# CW32F030C8T6.net
KiCad netlist of a schematic drawn in EasyEDA Pro
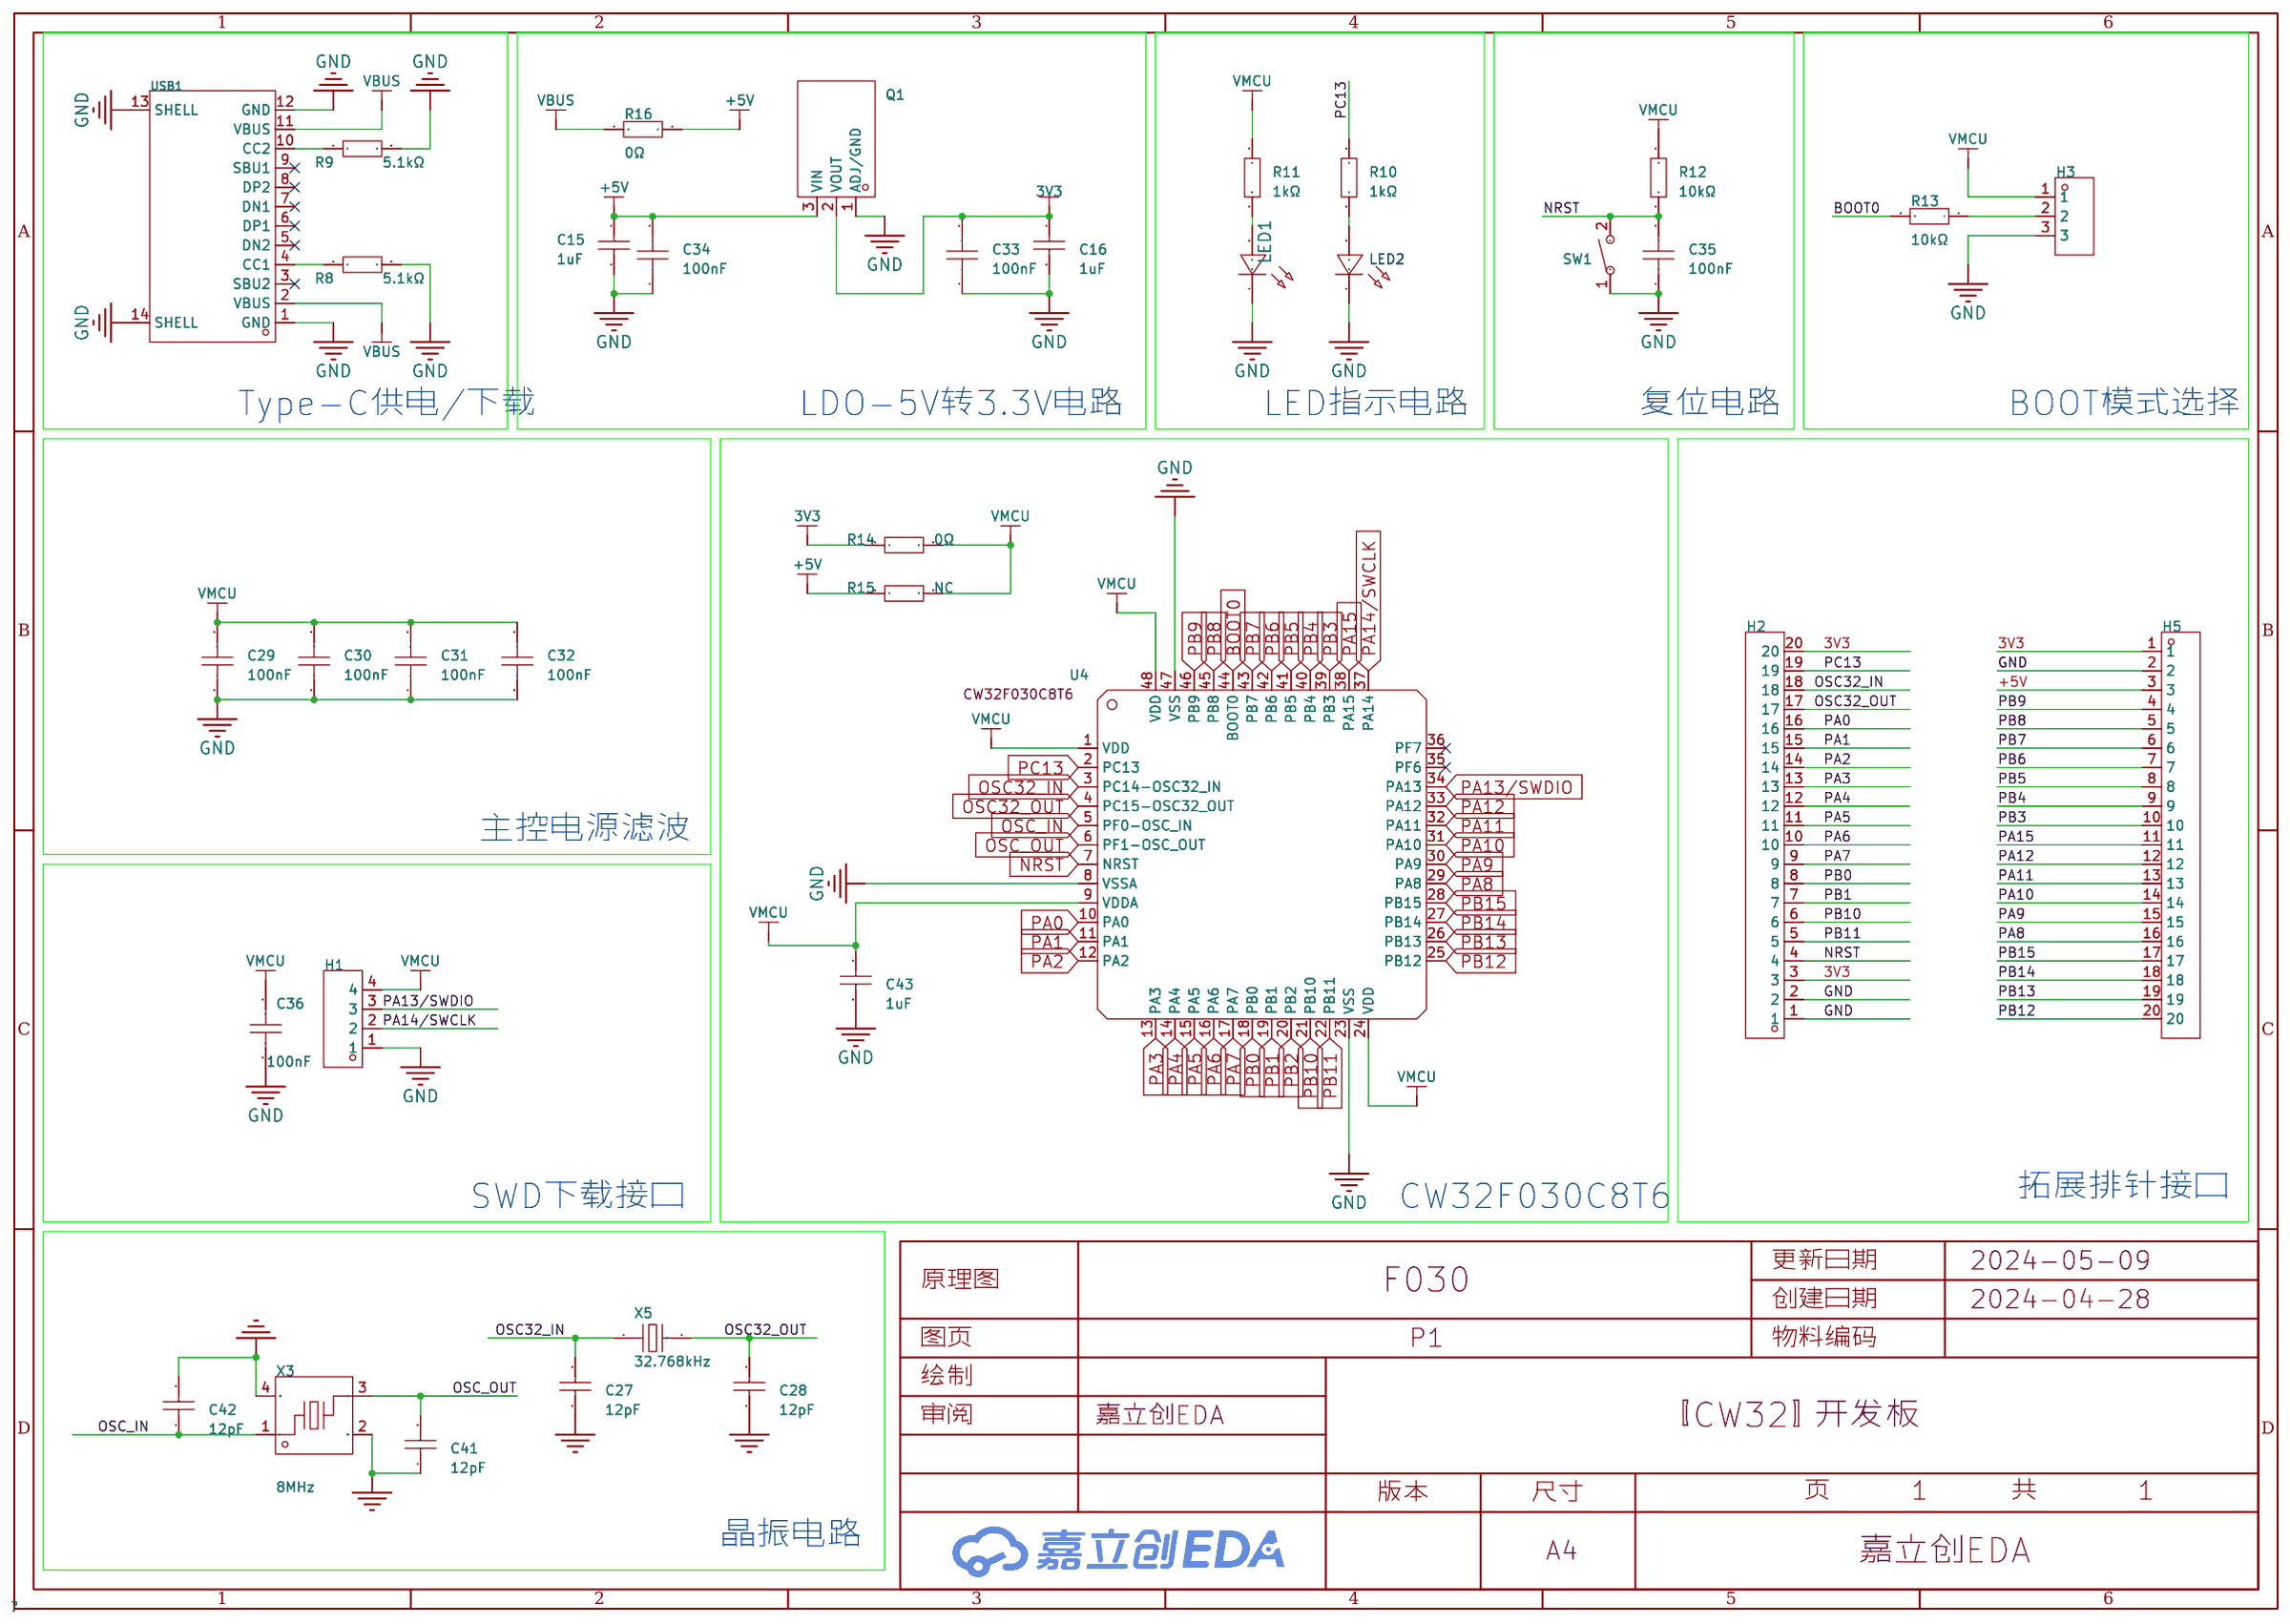
[diagram p0: schematic sheet]

(export (version "E")
  (design (tool "Eeschema 10.0.6"))
  (components
    (comp (ref "C15")
      (value "1uF")
      (footprint "easyedapro:C0402")
      (description "容值:1uF;精度:±10%;额定电压:10V;材质(温度系数):X5R;")
      (fields
        (field (name "Manufacturer Part") "CL10A105KO8NNNC")
        (field (name "Manufacturer") "SAMSUNG(三星)")
      )
      (libsource (lib "easyedapro") (part "CL05A105KP5NNNC"))
    )
    (comp (ref "C16")
      (value "1uF")
      (footprint "easyedapro:C0402")
      (description "容值:1uF;精度:±10%;额定电压:10V;材质(温度系数):X5R;")
      (fields
        (field (name "Manufacturer Part") "CL05A105KP5NNNC")
        (field (name "Manufacturer") "SAMSUNG(三星)")
      )
      (libsource (lib "easyedapro") (part "CL05A105KP5NNNC"))
    )
    (comp (ref "C27")
      (value "12pF")
      (footprint "easyedapro:C0402")
      (description "容值:12pF;精度:±5%;额定电压:50V;材质(温度系数):C0G;")
      (fields (field (name "Manufacturer Part") "0402CG120J500NT") (field (name "Manufacturer") "FH(风华)"))
      (libsource (lib "easyedapro") (part "0402CG120J500NT"))
    )
    (comp (ref "C28")
      (value "12pF")
      (footprint "easyedapro:C0402")
      (description "容值:12pF;精度:±5%;额定电压:50V;材质(温度系数):C0G;")
      (fields (field (name "Manufacturer Part") "0402CG120J500NT") (field (name "Manufacturer") "FH(风华)"))
      (libsource (lib "easyedapro") (part "0402CG120J500NT"))
    )
    (comp (ref "C29")
      (value "100nF")
      (footprint "easyedapro:C0402")
      (description "容值:100nF;精度:±10%;额定电压:50V;材质(温度系数):X7R;")
      (fields
        (field (name "Manufacturer Part") "GRM155R71H104KE14D")
        (field (name "Manufacturer") "muRata(村田)")
      )
      (libsource (lib "easyedapro") (part "GRM155R71H104KE14D"))
    )
    (comp (ref "C30")
      (value "100nF")
      (footprint "easyedapro:C0402")
      (description "容值:100nF;精度:±10%;额定电压:50V;材质(温度系数):X7R;")
      (fields
        (field (name "Manufacturer Part") "GRM155R71H104KE14D")
        (field (name "Manufacturer") "muRata(村田)")
      )
      (libsource (lib "easyedapro") (part "GRM155R71H104KE14D"))
    )
    (comp (ref "C31")
      (value "100nF")
      (footprint "easyedapro:C0402")
      (description "容值:100nF;精度:±10%;额定电压:50V;材质(温度系数):X7R;")
      (fields
        (field (name "Manufacturer Part") "GRM155R71H104KE14D")
        (field (name "Manufacturer") "muRata(村田)")
      )
      (libsource (lib "easyedapro") (part "GRM155R71H104KE14D"))
    )
    (comp (ref "C32")
      (value "100nF")
      (footprint "easyedapro:C0402")
      (description "容值:100nF;精度:±10%;额定电压:50V;材质(温度系数):X7R;")
      (fields
        (field (name "Manufacturer Part") "GRM155R71H104KE14D")
        (field (name "Manufacturer") "muRata(村田)")
      )
      (libsource (lib "easyedapro") (part "GRM155R71H104KE14D"))
    )
    (comp (ref "C33")
      (value "100nF")
      (footprint "easyedapro:C0402")
      (description "容值:100nF;精度:±10%;额定电压:50V;材质(温度系数):X7R;")
      (fields
        (field (name "Manufacturer Part") "GRM155R71H104KE14D")
        (field (name "Manufacturer") "muRata(村田)")
      )
      (libsource (lib "easyedapro") (part "GRM155R71H104KE14D"))
    )
    (comp (ref "C34")
      (value "100nF")
      (footprint "easyedapro:C0402")
      (description "容值:100nF;精度:±10%;额定电压:50V;材质(温度系数):X7R;")
      (fields
        (field (name "Manufacturer Part") "CC0603KRX7R9BB104")
        (field (name "Manufacturer") "YAGEO(国巨)")
      )
      (libsource (lib "easyedapro") (part "GRM155R71H104KE14D"))
    )
    (comp (ref "C35")
      (value "100nF")
      (footprint "easyedapro:C0402")
      (description "容值:100nF;精度:±10%;额定电压:50V;材质(温度系数):X7R;")
      (fields
        (field (name "Manufacturer Part") "GRM155R71H104KE14D")
        (field (name "Manufacturer") "muRata(村田)")
      )
      (libsource (lib "easyedapro") (part "GRM155R71H104KE14D"))
    )
    (comp (ref "C36")
      (value "100nF")
      (footprint "easyedapro:C0402")
      (description "容值:100nF;精度:±10%;额定电压:50V;材质(温度系数):X7R;")
      (fields
        (field (name "Manufacturer Part") "GRM155R71H104KE14D")
        (field (name "Manufacturer") "muRata(村田)")
      )
      (libsource (lib "easyedapro") (part "GRM155R71H104KE14D"))
    )
    (comp (ref "C41")
      (value "12pF")
      (footprint "easyedapro:C0402")
      (description "容值:12pF;精度:±5%;额定电压:50V;材质(温度系数):C0G;")
      (fields (field (name "Manufacturer Part") "0402CG120J500NT") (field (name "Manufacturer") "FH(风华)"))
      (libsource (lib "easyedapro") (part "0402CG120J500NT"))
    )
    (comp (ref "C42")
      (value "12pF")
      (footprint "easyedapro:C0402")
      (description "容值:12pF;精度:±5%;额定电压:50V;材质(温度系数):C0G;")
      (fields (field (name "Manufacturer Part") "0402CG120J500NT") (field (name "Manufacturer") "FH(风华)"))
      (libsource (lib "easyedapro") (part "0402CG120J500NT"))
    )
    (comp (ref "C43")
      (value "1uF")
      (footprint "easyedapro:C0402")
      (description "容值:1uF;精度:±10%;额定电压:10V;材质(温度系数):X5R;")
      (fields
        (field (name "Manufacturer Part") "CL05A105KP5NNNC")
        (field (name "Manufacturer") "SAMSUNG(三星)")
      )
      (libsource (lib "easyedapro") (part "CL05A105KP5NNNC"))
    )
    (comp (ref "H1")
      (value "~")
      (footprint "easyedapro:HDR-TH_4P-P2.54-V-M")
      (libsource (lib "easyedapro") (part "PZ254V-11-04P"))
    )
    (comp (ref "H2")
      (value "~")
      (footprint "easyedapro:HDR-TH_20P-P2.54-V-M-1")
      (libsource (lib "easyedapro") (part "HDR_2.54-1x20P"))
    )
    (comp (ref "H3")
      (value "~")
      (footprint "easyedapro:HDR-TH_3P-P2.54-V-M")
      (libsource (lib "easyedapro") (part "PZ254V-11-03P_C2937625"))
    )
    (comp (ref "H5")
      (value "~")
      (footprint "easyedapro:HDR-TH_20P-P2.54-V-M-1")
      (libsource (lib "easyedapro") (part "HDR_2.54-1x20P"))
    )
    (comp (ref "LED1")
      (value "~")
      (footprint "easyedapro:LED_0603")
      (libsource (lib "easyedapro") (part "LED_R"))
    )
    (comp (ref "LED2")
      (value "~")
      (footprint "easyedapro:LED_0603")
      (libsource (lib "easyedapro") (part "LED_B"))
    )
    (comp (ref "Q1")
      (value "AMS1117-3.3V")
      (footprint "easyedapro:SOT-89-3_L4.5-W2.5-P1.50-LS4.2-BR")
      (description "输出类型:固定;最大输入电压:18V;输出电压:3.3V;最大输出电流:1A;输出极性:正极;")
      (fields (field (name "Manufacturer") "MSKSEMI(美森科)"))
      (libsource (lib "easyedapro") (part "AMS1117-3.3V_C5120796"))
    )
    (comp (ref "R8")
      (value "5.1kΩ")
      (footprint "easyedapro:R0402")
      (description "电阻类型:厚膜电阻;阻值:5.1kΩ;精度:±1%;功率:62.5mW;最大工作电压:50V;温度系数:±100ppm/°C;")
      (fields
        (field (name "Manufacturer Part") "0402WGF5101TCE")
        (field (name "Manufacturer") "UNI-ROYAL(厚声)")
      )
      (libsource (lib "easyedapro") (part "0402WGF5101TCE"))
    )
    (comp (ref "R9")
      (value "5.1kΩ")
      (footprint "easyedapro:R0402")
      (description "电阻类型:厚膜电阻;阻值:5.1kΩ;精度:±1%;功率:62.5mW;最大工作电压:50V;温度系数:±100ppm/°C;")
      (fields
        (field (name "Manufacturer Part") "0402WGF5101TCE")
        (field (name "Manufacturer") "UNI-ROYAL(厚声)")
      )
      (libsource (lib "easyedapro") (part "0402WGF5101TCE"))
    )
    (comp (ref "R10")
      (value "1kΩ")
      (footprint "easyedapro:R0402")
      (description "电阻类型:厚膜电阻;阻值:1kΩ;精度:±1%;功率:62.5mW;最大工作电压:50V;温度系数:±100ppm/°C;")
      (fields
        (field (name "Manufacturer Part") "0402WGF1001TCE")
        (field (name "Manufacturer") "UNI-ROYAL(厚声)")
      )
      (libsource (lib "easyedapro") (part "0402WGF1001TCE"))
    )
    (comp (ref "R11")
      (value "1kΩ")
      (footprint "easyedapro:R0402")
      (description "电阻类型:厚膜电阻;阻值:1kΩ;精度:±1%;功率:62.5mW;最大工作电压:50V;温度系数:±100ppm/°C;")
      (fields
        (field (name "Manufacturer Part") "0402WGF1001TCE")
        (field (name "Manufacturer") "UNI-ROYAL(厚声)")
      )
      (libsource (lib "easyedapro") (part "0402WGF1001TCE"))
    )
    (comp (ref "R12")
      (value "10kΩ")
      (footprint "easyedapro:R0402")
      (description "电阻类型:厚膜电阻;阻值:10kΩ;精度:±1%;功率:62.5mW;最大工作电压:50V;温度系数:±100ppm/°C;")
      (fields (field (name "Manufacturer Part") "RC0402FR-0710KL") (field (name "Manufacturer") "YAGEO(国巨)"))
      (libsource (lib "easyedapro") (part "RC0402FR-0710KL"))
    )
    (comp (ref "R13")
      (value "10kΩ")
      (footprint "easyedapro:R0402")
      (description "电阻类型:厚膜电阻;阻值:10kΩ;精度:±1%;功率:62.5mW;最大工作电压:50V;温度系数:±100ppm/°C;")
      (fields (field (name "Manufacturer Part") "RC0402FR-0710KL") (field (name "Manufacturer") "YAGEO(国巨)"))
      (libsource (lib "easyedapro") (part "RC0402FR-0710KL"))
    )
    (comp (ref "R14")
      (value "0Ω")
      (footprint "easyedapro:R0805")
      (description "电阻类型:厚膜电阻;阻值:0Ω;精度:±1%;功率:125mW;最大工作电压:150V;温度系数:±800ppm/°C;")
      (fields
        (field (name "Manufacturer Part") "0805W8F0000T5E")
        (field (name "Manufacturer") "UNI-ROYAL(厚声)")
      )
      (libsource (lib "easyedapro") (part "0805W8F0000T5E"))
    )
    (comp (ref "R15")
      (value "NC")
      (footprint "easyedapro:R0805")
      (description "电阻类型:厚膜电阻;阻值:0Ω;精度:±1%;功率:125mW;最大工作电压:150V;温度系数:±800ppm/°C;")
      (fields
        (field (name "Manufacturer Part") "0805W8F0000T5E")
        (field (name "Manufacturer") "UNI-ROYAL(厚声)")
      )
      (libsource (lib "easyedapro") (part "0805W8F0000T5E"))
    )
    (comp (ref "R16")
      (value "0Ω")
      (footprint "easyedapro:R0603")
      (description "电阻类型:厚膜电阻;阻值:0Ω;精度:±1%;功率:100mW;最大工作电压:75V;")
      (fields
        (field (name "Manufacturer Part") "0603WAF0000T5E")
        (field (name "Manufacturer") "UNI-ROYAL(厚声)")
      )
      (libsource (lib "easyedapro") (part "0603WAF0000T5E"))
    )
    (comp (ref "SW1")
      (value "TS-1101-B-W")
      (footprint "easyedapro:KEY-SMD_2P-L6.0-W3.6-P7.4-LS8.0-L")
      (description "触点电流:50mA;额定电压(DC):12V;绝缘电阻:-;电路结构:单刀单掷;安装方式:立贴;带灯:无;作用力:160gf;机械寿命:5万次;带支架:否;")
      (fields (field (name "Manufacturer") "XKB Connectivity(中国星坤)"))
      (libsource (lib "easyedapro") (part "TS-1101-B-W"))
    )
    (comp (ref "U4")
      (value "CW32F030C8T6")
      (footprint "easyedapro:LQFP-48_L7.0-W7.0-P0.50-LS9.0-TL")
      (description "CPU内核:ARM-M系列;RAM总容量:8KB;GPIO端口数量:39;工作电压范围:1.65V~5.5V;CPU最大主频:64MHz;程序存储器类型:-;")
      (fields (field (name "Manufacturer Part") "CW32F030C8T6") (field (name "Manufacturer") "CW(芯源)"))
      (libsource (lib "easyedapro") (part "CW32F030C8T6_C3019113"))
    )
    (comp (ref "USB1")
      (value "TYPE-C 16PIN 2MD(073)")
      (footprint "easyedapro:USB-C-SMD_TYPE-C-6PIN-2MD-073")
      (description "连接器类型:Type-C;标准:-;公母:母座;触点数量:16;端口数量:1;安装方式:卧贴;额定电流 - 电源:5A;工作温度范围:-25°C~+85°C;")
      (fields (field (name "Manufacturer") "SHOU HAN(首韩)"))
      (libsource (lib "easyedapro") (part "TYPE-C 16PIN 2MD(073)"))
    )
    (comp (ref "X3")
      (value "8MHz")
      (footprint "easyedapro:CRYSTAL-SMD_4P-L3.2-W2.5-BL-1")
      (description "晶振类型:贴片晶振;频率:8MHz;常温频差:±10ppm;外接负载电容:12pF;频率稳定度(全温):±20ppm;")
      (fields
        (field (name "Manufacturer Part") "XL2EL89COI-111YLC-8M")
        (field (name "Manufacturer") "YXC(扬兴晶振)")
      )
      (libsource (lib "easyedapro") (part "XL2EL89COI-111YLC-8M"))
    )
    (comp (ref "X5")
      (value "32.768kHz")
      (footprint "easyedapro:OSC-SMD_L3.2-W1.5")
      (description "晶振类型:贴片晶振;频率:32.768kHz;常温频差:±20ppm;外接负载电容:12.5pF;频率稳定度(全温):-;")
      (fields (field (name "Manufacturer Part") "X321532768KGD2SI") (field (name "Manufacturer") "YXC(扬兴晶振)"))
      (libsource (lib "easyedapro") (part "X321532768KGD2SI"))
    )
  )
  (nets
    (net (code "1") (name "+5V") (class "Default")
      (node (ref "C15") (pin "2") (pinfunction "2_2") (pintype "input"))
      (node (ref "C34") (pin "2") (pinfunction "2_2") (pintype "unspecified"))
      (node (ref "H5") (pin "3") (pinfunction "3_3") (pintype "input"))
      (node (ref "Q1") (pin "3") (pinfunction "VIN_3") (pintype "unspecified"))
      (node (ref "R15") (pin "1") (pinfunction "1_1") (pintype "input"))
      (node (ref "R16") (pin "2") (pinfunction "2_2") (pintype "input"))
    )
    (net (code "2") (name "3V3") (class "Default")
      (node (ref "C16") (pin "2") (pinfunction "2_2") (pintype "input"))
      (node (ref "C33") (pin "2") (pinfunction "2_2") (pintype "unspecified"))
      (node (ref "H2") (pin "20") (pinfunction "20_20") (pintype "input"))
      (node (ref "H2") (pin "3") (pinfunction "3_3") (pintype "input"))
      (node (ref "H5") (pin "1") (pinfunction "1_1") (pintype "input"))
      (node (ref "Q1") (pin "2") (pinfunction "VOUT_2") (pintype "unspecified"))
      (node (ref "R14") (pin "1") (pinfunction "1_1") (pintype "input"))
    )
    (net (code "3") (name "BOOT0") (class "Default")
      (node (ref "R13") (pin "2") (pinfunction "2_2") (pintype "input"))
      (node (ref "U4") (pin "44") (pinfunction "BOOT0_44") (pintype "unspecified"))
    )
    (net (code "4") (name "GND") (class "Default")
      (node (ref "C15") (pin "1") (pinfunction "1_1") (pintype "input"))
      (node (ref "C16") (pin "1") (pinfunction "1_1") (pintype "input"))
      (node (ref "C27") (pin "1") (pinfunction "1_1") (pintype "input"))
      (node (ref "C28") (pin "1") (pinfunction "1_1") (pintype "input"))
      (node (ref "C29") (pin "1") (pinfunction "1_1") (pintype "unspecified"))
      (node (ref "C30") (pin "1") (pinfunction "1_1") (pintype "unspecified"))
      (node (ref "C31") (pin "1") (pinfunction "1_1") (pintype "unspecified"))
      (node (ref "C32") (pin "1") (pinfunction "1_1") (pintype "unspecified"))
      (node (ref "C33") (pin "1") (pinfunction "1_1") (pintype "unspecified"))
      (node (ref "C34") (pin "1") (pinfunction "1_1") (pintype "unspecified"))
      (node (ref "C35") (pin "1") (pinfunction "1_1") (pintype "unspecified"))
      (node (ref "C36") (pin "1") (pinfunction "1_1") (pintype "unspecified"))
      (node (ref "C41") (pin "1") (pinfunction "1_1") (pintype "input"))
      (node (ref "C42") (pin "2") (pinfunction "2_2") (pintype "input"))
      (node (ref "C43") (pin "1") (pinfunction "1_1") (pintype "input"))
      (node (ref "H1") (pin "1") (pinfunction "1_1") (pintype "input"))
      (node (ref "H2") (pin "1") (pinfunction "1_1") (pintype "input"))
      (node (ref "H2") (pin "2") (pinfunction "2_2") (pintype "input"))
      (node (ref "H3") (pin "3") (pinfunction "3_3") (pintype "input"))
      (node (ref "H5") (pin "2") (pinfunction "2_2") (pintype "input"))
      (node (ref "LED1") (pin "1") (pinfunction "C_1") (pintype "input"))
      (node (ref "LED2") (pin "1") (pinfunction "C_1") (pintype "input"))
      (node (ref "Q1") (pin "1") (pinfunction "ADJ/GND_1") (pintype "unspecified"))
      (node (ref "R8") (pin "2") (pinfunction "2_2") (pintype "input"))
      (node (ref "R9") (pin "2") (pinfunction "2_2") (pintype "input"))
      (node (ref "SW1") (pin "1") (pinfunction "1_1") (pintype "input"))
      (node (ref "U4") (pin "23") (pinfunction "VSS_23") (pintype "unspecified"))
      (node (ref "U4") (pin "47") (pinfunction "VSS_47") (pintype "unspecified"))
      (node (ref "U4") (pin "8") (pinfunction "VSSA_8") (pintype "unspecified"))
      (node (ref "USB1") (pin "1") (pinfunction "GND_1") (pintype "input"))
      (node (ref "USB1") (pin "12") (pinfunction "GND_12") (pintype "input"))
      (node (ref "USB1") (pin "13") (pinfunction "SHELL_13") (pintype "input"))
      (node (ref "USB1") (pin "14") (pinfunction "SHELL_14") (pintype "input"))
      (node (ref "X3") (pin "2") (pinfunction "GND_2") (pintype "input"))
      (node (ref "X3") (pin "4") (pinfunction "GND_4") (pintype "input"))
    )
    (net (code "5") (name "NRST") (class "Default")
      (node (ref "C35") (pin "2") (pinfunction "2_2") (pintype "unspecified"))
      (node (ref "H2") (pin "4") (pinfunction "4_4") (pintype "input"))
      (node (ref "R12") (pin "1") (pinfunction "1_1") (pintype "input"))
      (node (ref "SW1") (pin "2") (pinfunction "2_2") (pintype "input"))
      (node (ref "U4") (pin "7") (pinfunction "NRST_7") (pintype "unspecified"))
    )
    (net (code "6") (name "Net-(H3-Pad2)") (class "Default")
      (node (ref "H3") (pin "2") (pinfunction "2_2") (pintype "input"))
      (node (ref "R13") (pin "1") (pinfunction "1_1") (pintype "input"))
    )
    (net (code "7") (name "Net-(LED1-A)") (class "Default")
      (node (ref "LED1") (pin "2") (pinfunction "A_2") (pintype "input"))
      (node (ref "R11") (pin "2") (pinfunction "2_2") (pintype "input"))
    )
    (net (code "8") (name "Net-(LED2-A)") (class "Default")
      (node (ref "LED2") (pin "2") (pinfunction "A_2") (pintype "input"))
      (node (ref "R10") (pin "1") (pinfunction "1_1") (pintype "input"))
    )
    (net (code "9") (name "Net-(USB1-CC1)") (class "Default")
      (node (ref "R8") (pin "1") (pinfunction "1_1") (pintype "input"))
      (node (ref "USB1") (pin "4") (pinfunction "CC1_4") (pintype "input"))
    )
    (net (code "10") (name "Net-(USB1-CC2)") (class "Default")
      (node (ref "R9") (pin "1") (pinfunction "1_1") (pintype "input"))
      (node (ref "USB1") (pin "10") (pinfunction "CC2_10") (pintype "input"))
    )
    (net (code "11") (name "OSC32_IN") (class "Default")
      (node (ref "C27") (pin "2") (pinfunction "2_2") (pintype "input"))
      (node (ref "H2") (pin "18") (pinfunction "18_18") (pintype "input"))
      (node (ref "U4") (pin "3") (pinfunction "PC14-OSC32_IN_3") (pintype "unspecified"))
      (node (ref "X5") (pin "1") (pinfunction "1_1") (pintype "input"))
    )
    (net (code "12") (name "OSC32_OUT") (class "Default")
      (node (ref "C28") (pin "2") (pinfunction "2_2") (pintype "input"))
      (node (ref "H2") (pin "17") (pinfunction "17_17") (pintype "input"))
      (node (ref "U4") (pin "4") (pinfunction "PC15-OSC32_OUT_4") (pintype "unspecified"))
      (node (ref "X5") (pin "2") (pinfunction "2_2") (pintype "input"))
    )
    (net (code "13") (name "OSC_IN") (class "Default")
      (node (ref "C42") (pin "1") (pinfunction "1_1") (pintype "input"))
      (node (ref "U4") (pin "5") (pinfunction "PF0-OSC_IN_5") (pintype "unspecified"))
      (node (ref "X3") (pin "1") (pinfunction "1_1") (pintype "input"))
    )
    (net (code "14") (name "OSC_OUT") (class "Default")
      (node (ref "C41") (pin "2") (pinfunction "2_2") (pintype "input"))
      (node (ref "U4") (pin "6") (pinfunction "PF1-OSC_OUT_6") (pintype "unspecified"))
      (node (ref "X3") (pin "3") (pinfunction "3_3") (pintype "input"))
    )
    (net (code "15") (name "PA0") (class "Default")
      (node (ref "H2") (pin "16") (pinfunction "16_16") (pintype "input"))
      (node (ref "U4") (pin "10") (pinfunction "PA0_10") (pintype "unspecified"))
    )
    (net (code "16") (name "PA1") (class "Default")
      (node (ref "H2") (pin "15") (pinfunction "15_15") (pintype "input"))
      (node (ref "U4") (pin "11") (pinfunction "PA1_11") (pintype "unspecified"))
    )
    (net (code "17") (name "PA2") (class "Default")
      (node (ref "H2") (pin "14") (pinfunction "14_14") (pintype "input"))
      (node (ref "U4") (pin "12") (pinfunction "PA2_12") (pintype "unspecified"))
    )
    (net (code "18") (name "PA3") (class "Default")
      (node (ref "H2") (pin "13") (pinfunction "13_13") (pintype "input"))
      (node (ref "U4") (pin "13") (pinfunction "PA3_13") (pintype "unspecified"))
    )
    (net (code "19") (name "PA4") (class "Default")
      (node (ref "H2") (pin "12") (pinfunction "12_12") (pintype "input"))
      (node (ref "U4") (pin "14") (pinfunction "PA4_14") (pintype "unspecified"))
    )
    (net (code "20") (name "PA5") (class "Default")
      (node (ref "H2") (pin "11") (pinfunction "11_11") (pintype "input"))
      (node (ref "U4") (pin "15") (pinfunction "PA5_15") (pintype "unspecified"))
    )
    (net (code "21") (name "PA6") (class "Default")
      (node (ref "H2") (pin "10") (pinfunction "10_10") (pintype "input"))
      (node (ref "U4") (pin "16") (pinfunction "PA6_16") (pintype "unspecified"))
    )
    (net (code "22") (name "PA7") (class "Default")
      (node (ref "H2") (pin "9") (pinfunction "9_9") (pintype "input"))
      (node (ref "U4") (pin "17") (pinfunction "PA7_17") (pintype "unspecified"))
    )
    (net (code "23") (name "PA8") (class "Default")
      (node (ref "H5") (pin "16") (pinfunction "16_16") (pintype "input"))
      (node (ref "U4") (pin "29") (pinfunction "PA8_29") (pintype "unspecified"))
    )
    (net (code "24") (name "PA9") (class "Default")
      (node (ref "H5") (pin "15") (pinfunction "15_15") (pintype "input"))
      (node (ref "U4") (pin "30") (pinfunction "PA9_30") (pintype "unspecified"))
    )
    (net (code "25") (name "PA10") (class "Default")
      (node (ref "H5") (pin "14") (pinfunction "14_14") (pintype "input"))
      (node (ref "U4") (pin "31") (pinfunction "PA10_31") (pintype "unspecified"))
    )
    (net (code "26") (name "PA11") (class "Default")
      (node (ref "H5") (pin "13") (pinfunction "13_13") (pintype "input"))
      (node (ref "U4") (pin "32") (pinfunction "PA11_32") (pintype "unspecified"))
    )
    (net (code "27") (name "PA12") (class "Default")
      (node (ref "H5") (pin "12") (pinfunction "12_12") (pintype "input"))
      (node (ref "U4") (pin "33") (pinfunction "PA12_33") (pintype "unspecified"))
    )
    (net (code "28") (name "PA13{slash}SWDIO") (class "Default")
      (node (ref "H1") (pin "3") (pinfunction "3_3") (pintype "input"))
      (node (ref "U4") (pin "34") (pinfunction "PA13_34") (pintype "unspecified"))
    )
    (net (code "29") (name "PA14{slash}SWCLK") (class "Default")
      (node (ref "H1") (pin "2") (pinfunction "2_2") (pintype "input"))
      (node (ref "U4") (pin "37") (pinfunction "PA14_37") (pintype "unspecified"))
    )
    (net (code "30") (name "PA15") (class "Default")
      (node (ref "H5") (pin "11") (pinfunction "11_11") (pintype "input"))
      (node (ref "U4") (pin "38") (pinfunction "PA15_38") (pintype "unspecified"))
    )
    (net (code "31") (name "PB0") (class "Default")
      (node (ref "H2") (pin "8") (pinfunction "8_8") (pintype "input"))
      (node (ref "U4") (pin "18") (pinfunction "PB0_18") (pintype "unspecified"))
    )
    (net (code "32") (name "PB1") (class "Default")
      (node (ref "H2") (pin "7") (pinfunction "7_7") (pintype "input"))
      (node (ref "U4") (pin "19") (pinfunction "PB1_19") (pintype "unspecified"))
    )
    (net (code "33") (name "PB2") (class "Default")
      (node (ref "U4") (pin "20") (pinfunction "PB2_20") (pintype "unspecified"))
    )
    (net (code "34") (name "PB3") (class "Default")
      (node (ref "H5") (pin "10") (pinfunction "10_10") (pintype "input"))
      (node (ref "U4") (pin "39") (pinfunction "PB3_39") (pintype "unspecified"))
    )
    (net (code "35") (name "PB4") (class "Default")
      (node (ref "H5") (pin "9") (pinfunction "9_9") (pintype "input"))
      (node (ref "U4") (pin "40") (pinfunction "PB4_40") (pintype "unspecified"))
    )
    (net (code "36") (name "PB5") (class "Default")
      (node (ref "H5") (pin "8") (pinfunction "8_8") (pintype "input"))
      (node (ref "U4") (pin "41") (pinfunction "PB5_41") (pintype "unspecified"))
    )
    (net (code "37") (name "PB6") (class "Default")
      (node (ref "H5") (pin "7") (pinfunction "7_7") (pintype "input"))
      (node (ref "U4") (pin "42") (pinfunction "PB6_42") (pintype "unspecified"))
    )
    (net (code "38") (name "PB7") (class "Default")
      (node (ref "H5") (pin "6") (pinfunction "6_6") (pintype "input"))
      (node (ref "U4") (pin "43") (pinfunction "PB7_43") (pintype "unspecified"))
    )
    (net (code "39") (name "PB8") (class "Default")
      (node (ref "H5") (pin "5") (pinfunction "5_5") (pintype "input"))
      (node (ref "U4") (pin "45") (pinfunction "PB8_45") (pintype "unspecified"))
    )
    (net (code "40") (name "PB9") (class "Default")
      (node (ref "H5") (pin "4") (pinfunction "4_4") (pintype "input"))
      (node (ref "U4") (pin "46") (pinfunction "PB9_46") (pintype "unspecified"))
    )
    (net (code "41") (name "PB10") (class "Default")
      (node (ref "H2") (pin "6") (pinfunction "6_6") (pintype "input"))
      (node (ref "U4") (pin "21") (pinfunction "PB10_21") (pintype "unspecified"))
    )
    (net (code "42") (name "PB11") (class "Default")
      (node (ref "H2") (pin "5") (pinfunction "5_5") (pintype "input"))
      (node (ref "U4") (pin "22") (pinfunction "PB11_22") (pintype "unspecified"))
    )
    (net (code "43") (name "PB12") (class "Default")
      (node (ref "H5") (pin "20") (pinfunction "20_20") (pintype "input"))
      (node (ref "U4") (pin "25") (pinfunction "PB12_25") (pintype "unspecified"))
    )
    (net (code "44") (name "PB13") (class "Default")
      (node (ref "H5") (pin "19") (pinfunction "19_19") (pintype "input"))
      (node (ref "U4") (pin "26") (pinfunction "PB13_26") (pintype "unspecified"))
    )
    (net (code "45") (name "PB14") (class "Default")
      (node (ref "H5") (pin "18") (pinfunction "18_18") (pintype "input"))
      (node (ref "U4") (pin "27") (pinfunction "PB14_27") (pintype "unspecified"))
    )
    (net (code "46") (name "PB15") (class "Default")
      (node (ref "H5") (pin "17") (pinfunction "17_17") (pintype "input"))
      (node (ref "U4") (pin "28") (pinfunction "PB15_28") (pintype "unspecified"))
    )
    (net (code "47") (name "PC13") (class "Default")
      (node (ref "H2") (pin "19") (pinfunction "19_19") (pintype "input"))
      (node (ref "R10") (pin "2") (pinfunction "2_2") (pintype "input"))
      (node (ref "U4") (pin "2") (pinfunction "PC13_2") (pintype "unspecified"))
    )
    (net (code "48") (name "VBUS") (class "Default")
      (node (ref "R16") (pin "1") (pinfunction "1_1") (pintype "input"))
      (node (ref "USB1") (pin "11") (pinfunction "VBUS_11") (pintype "input"))
      (node (ref "USB1") (pin "2") (pinfunction "VBUS_2") (pintype "input"))
    )
    (net (code "49") (name "VMCU") (class "Default")
      (node (ref "C29") (pin "2") (pinfunction "2_2") (pintype "unspecified"))
      (node (ref "C30") (pin "2") (pinfunction "2_2") (pintype "unspecified"))
      (node (ref "C31") (pin "2") (pinfunction "2_2") (pintype "unspecified"))
      (node (ref "C32") (pin "2") (pinfunction "2_2") (pintype "unspecified"))
      (node (ref "C36") (pin "2") (pinfunction "2_2") (pintype "unspecified"))
      (node (ref "C43") (pin "2") (pinfunction "2_2") (pintype "input"))
      (node (ref "H1") (pin "4") (pinfunction "4_4") (pintype "input"))
      (node (ref "H3") (pin "1") (pinfunction "1_1") (pintype "input"))
      (node (ref "R11") (pin "1") (pinfunction "1_1") (pintype "input"))
      (node (ref "R12") (pin "2") (pinfunction "2_2") (pintype "input"))
      (node (ref "R14") (pin "2") (pinfunction "2_2") (pintype "input"))
      (node (ref "R15") (pin "2") (pinfunction "2_2") (pintype "input"))
      (node (ref "U4") (pin "1") (pinfunction "VDD_1") (pintype "unspecified"))
      (node (ref "U4") (pin "24") (pinfunction "VDD_24") (pintype "unspecified"))
      (node (ref "U4") (pin "48") (pinfunction "VDD_48") (pintype "unspecified"))
      (node (ref "U4") (pin "9") (pinfunction "VDDA_9") (pintype "unspecified"))
    )
    (net (code "50") (name "unconnected-(U4-PF6-Pad35)") (class "Default")
      (node (ref "U4") (pin "35") (pinfunction "PF6_35") (pintype "unspecified+no_connect"))
    )
    (net (code "51") (name "unconnected-(U4-PF7-Pad36)") (class "Default")
      (node (ref "U4") (pin "36") (pinfunction "PF7_36") (pintype "unspecified+no_connect"))
    )
    (net (code "52") (name "unconnected-(USB1-DN1-Pad7)") (class "Default")
      (node (ref "USB1") (pin "7") (pinfunction "DN1_7") (pintype "input+no_connect"))
    )
    (net (code "53") (name "unconnected-(USB1-DN2-Pad5)") (class "Default")
      (node (ref "USB1") (pin "5") (pinfunction "DN2_5") (pintype "input+no_connect"))
    )
    (net (code "54") (name "unconnected-(USB1-DP1-Pad6)") (class "Default")
      (node (ref "USB1") (pin "6") (pinfunction "DP1_6") (pintype "input+no_connect"))
    )
    (net (code "55") (name "unconnected-(USB1-DP2-Pad8)") (class "Default")
      (node (ref "USB1") (pin "8") (pinfunction "DP2_8") (pintype "input+no_connect"))
    )
    (net (code "56") (name "unconnected-(USB1-SBU1-Pad9)") (class "Default")
      (node (ref "USB1") (pin "9") (pinfunction "SBU1_9") (pintype "input+no_connect"))
    )
    (net (code "57") (name "unconnected-(USB1-SBU2-Pad3)") (class "Default")
      (node (ref "USB1") (pin "3") (pinfunction "SBU2_3") (pintype "input+no_connect"))
    )
  )
)
